# Shift_Register_2IO_Breakout.net
KiCad netlist of a schematic drawn in EAGLE
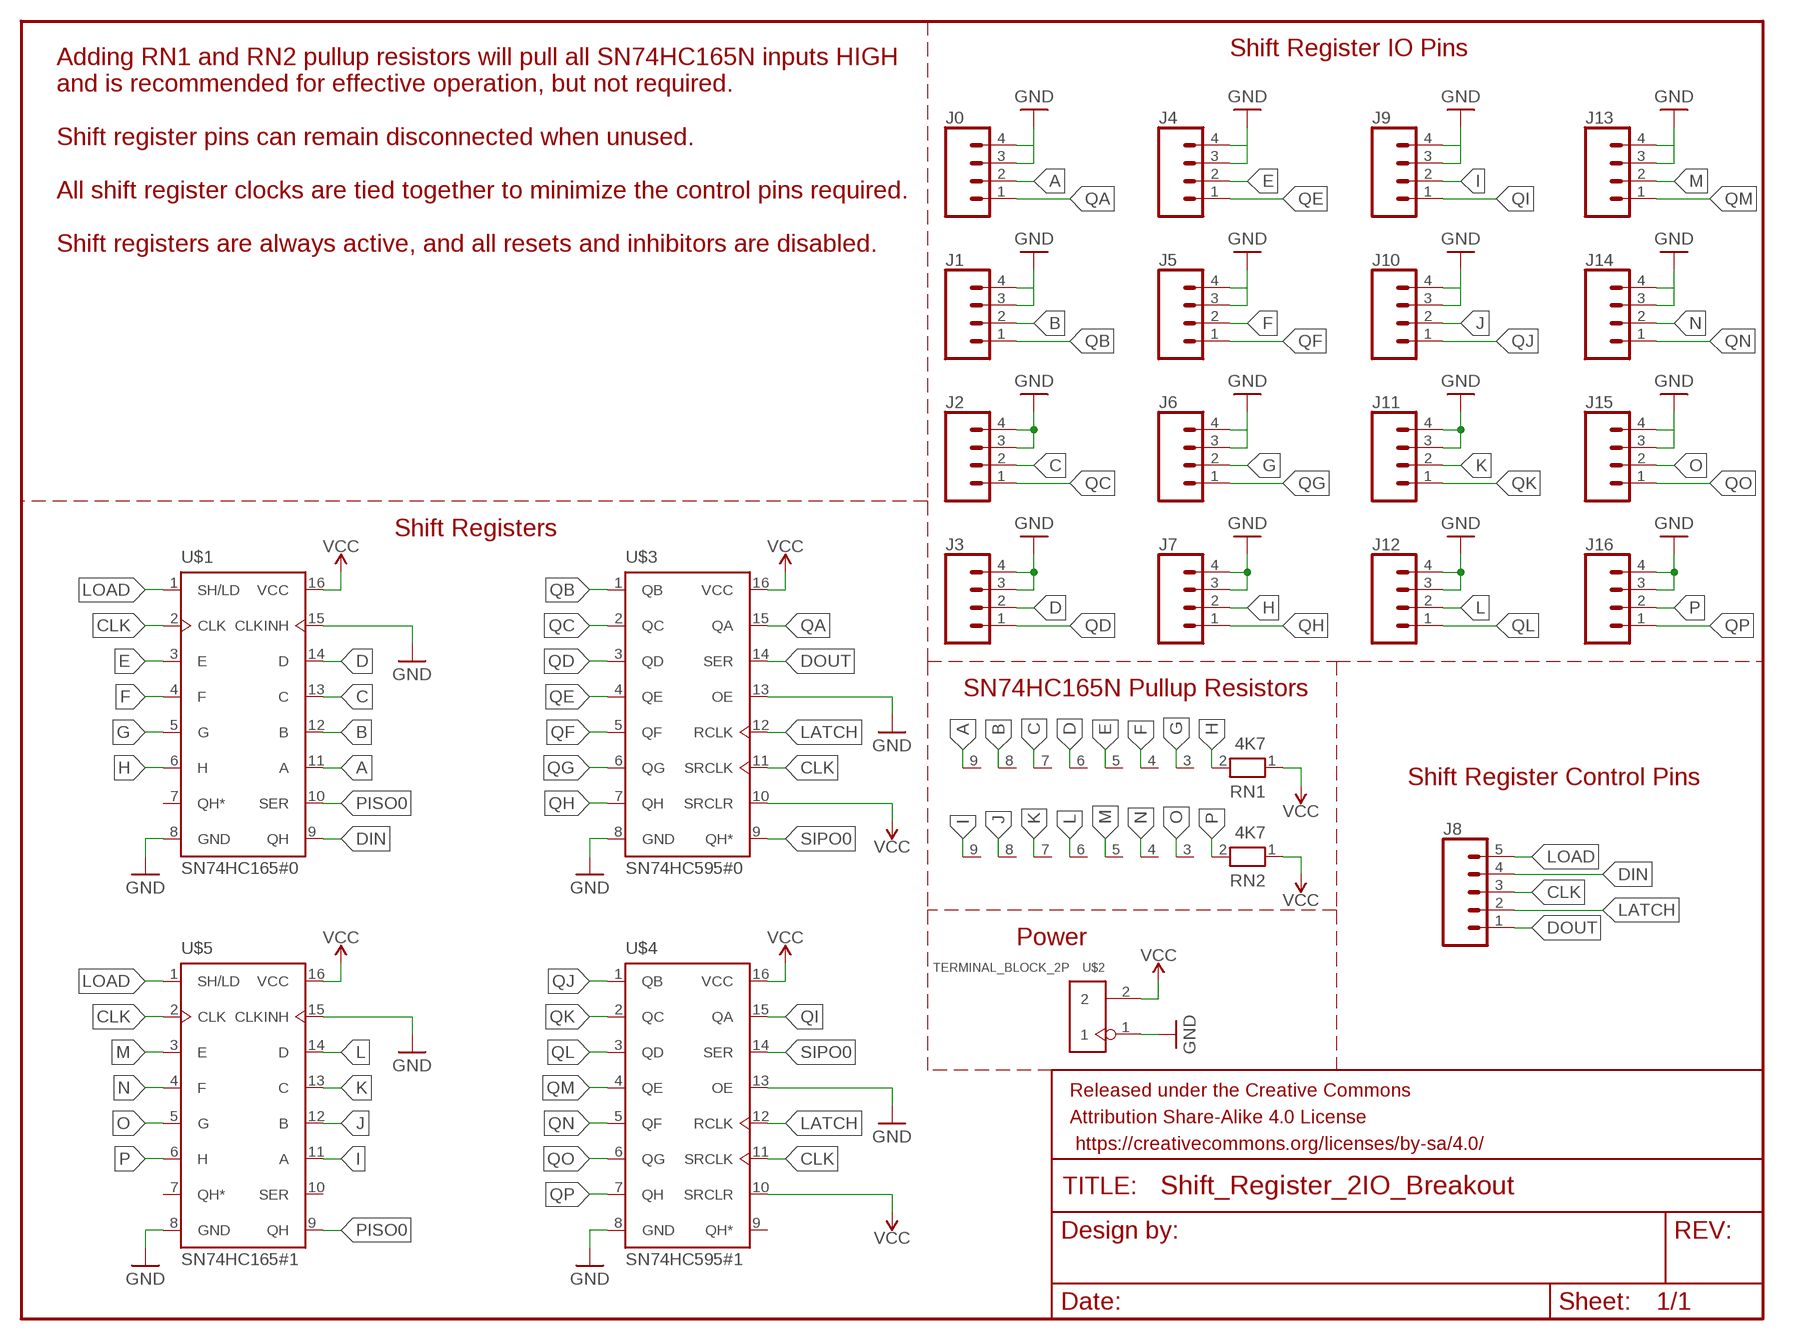
[diagram p0: schematic, sheet 1]

(export (version "E")
  (design (tool "Eeschema 10.0.6"))
  (components
    (comp (ref "FRAME2")
      (value "FRAME-LETTER")
      (footprint "eagle-import:CREATIVE_COMMONS")
      (libsource (lib "eagle-import") (part "FRAME-LETTER"))
    )
    (comp (ref "J0")
      (value "CONN_04")
      (footprint "eagle-import:1X04")
      (libsource (lib "eagle-import") (part "CONN_04"))
    )
    (comp (ref "J1")
      (value "CONN_04")
      (footprint "eagle-import:1X04")
      (libsource (lib "eagle-import") (part "CONN_04"))
    )
    (comp (ref "J2")
      (value "CONN_04")
      (footprint "eagle-import:1X04")
      (libsource (lib "eagle-import") (part "CONN_04"))
    )
    (comp (ref "J3")
      (value "CONN_04")
      (footprint "eagle-import:1X04")
      (libsource (lib "eagle-import") (part "CONN_04"))
    )
    (comp (ref "J4")
      (value "CONN_04")
      (footprint "eagle-import:1X04")
      (libsource (lib "eagle-import") (part "CONN_04"))
    )
    (comp (ref "J5")
      (value "CONN_04")
      (footprint "eagle-import:1X04")
      (libsource (lib "eagle-import") (part "CONN_04"))
    )
    (comp (ref "J6")
      (value "CONN_04")
      (footprint "eagle-import:1X04")
      (libsource (lib "eagle-import") (part "CONN_04"))
    )
    (comp (ref "J7")
      (value "CONN_04")
      (footprint "eagle-import:1X04")
      (libsource (lib "eagle-import") (part "CONN_04"))
    )
    (comp (ref "J8")
      (value "CONN_05")
      (footprint "eagle-import:1X05")
      (libsource (lib "eagle-import") (part "CONN_05"))
    )
    (comp (ref "J9")
      (value "CONN_04")
      (footprint "eagle-import:1X04")
      (libsource (lib "eagle-import") (part "CONN_04"))
    )
    (comp (ref "J10")
      (value "CONN_04")
      (footprint "eagle-import:1X04")
      (libsource (lib "eagle-import") (part "CONN_04"))
    )
    (comp (ref "J11")
      (value "CONN_04")
      (footprint "eagle-import:1X04")
      (libsource (lib "eagle-import") (part "CONN_04"))
    )
    (comp (ref "J12")
      (value "CONN_04")
      (footprint "eagle-import:1X04")
      (libsource (lib "eagle-import") (part "CONN_04"))
    )
    (comp (ref "J13")
      (value "CONN_04")
      (footprint "eagle-import:1X04")
      (libsource (lib "eagle-import") (part "CONN_04"))
    )
    (comp (ref "J14")
      (value "CONN_04")
      (footprint "eagle-import:1X04")
      (libsource (lib "eagle-import") (part "CONN_04"))
    )
    (comp (ref "J15")
      (value "CONN_04")
      (footprint "eagle-import:1X04")
      (libsource (lib "eagle-import") (part "CONN_04"))
    )
    (comp (ref "J16")
      (value "CONN_04")
      (footprint "eagle-import:1X04")
      (libsource (lib "eagle-import") (part "CONN_04"))
    )
    (comp (ref "RN1")
      (value "4K7")
      (footprint "eagle-import:RN-9")
      (libsource (lib "eagle-import") (part "RN08"))
    )
    (comp (ref "RN2")
      (value "4K7")
      (footprint "eagle-import:RN-9")
      (libsource (lib "eagle-import") (part "RN08"))
    )
    (comp (ref "U$1")
      (value "SN74HC165#0")
      (footprint "eagle-import:DIL16")
      (libsource (lib "eagle-import") (part "SN74HC165"))
    )
    (comp (ref "U$2")
      (value "TERMINAL_BLOCK_2P")
      (footprint "eagle-import:H2-5.0-10.5X8.0MM")
      (libsource (lib "eagle-import") (part "TERMINAL_BLOCK_2P"))
    )
    (comp (ref "U$3")
      (value "SN74HC595#0")
      (footprint "eagle-import:DIL16")
      (libsource (lib "eagle-import") (part "SN74HC595"))
    )
    (comp (ref "U$4")
      (value "SN74HC595#1")
      (footprint "eagle-import:DIL16")
      (libsource (lib "eagle-import") (part "SN74HC595"))
    )
    (comp (ref "U$5")
      (value "SN74HC165#1")
      (footprint "eagle-import:DIL16")
      (libsource (lib "eagle-import") (part "SN74HC165"))
    )
  )
  (nets
    (net (code "1") (name "A") (class "Default")
      (node (ref "J0") (pin "2") (pinfunction "2_2") (pintype "passive"))
      (node (ref "RN1") (pin "9") (pinfunction "9_9") (pintype "passive"))
      (node (ref "U$1") (pin "11") (pinfunction "A_11") (pintype "input"))
    )
    (net (code "2") (name "B") (class "Default")
      (node (ref "J1") (pin "2") (pinfunction "2_2") (pintype "passive"))
      (node (ref "RN1") (pin "8") (pinfunction "8_8") (pintype "passive"))
      (node (ref "U$1") (pin "12") (pinfunction "B_12") (pintype "input"))
    )
    (net (code "3") (name "C") (class "Default")
      (node (ref "J2") (pin "2") (pinfunction "2_2") (pintype "passive"))
      (node (ref "RN1") (pin "7") (pinfunction "7_7") (pintype "passive"))
      (node (ref "U$1") (pin "13") (pinfunction "C_13") (pintype "input"))
    )
    (net (code "4") (name "CLK") (class "Default")
      (node (ref "J8") (pin "3") (pinfunction "3_3") (pintype "passive"))
      (node (ref "U$1") (pin "2") (pinfunction "CLK_2") (pintype "input"))
      (node (ref "U$3") (pin "11") (pinfunction "SRCLK_11") (pintype "input"))
      (node (ref "U$4") (pin "11") (pinfunction "SRCLK_11") (pintype "input"))
      (node (ref "U$5") (pin "2") (pinfunction "CLK_2") (pintype "input"))
    )
    (net (code "5") (name "D") (class "Default")
      (node (ref "J3") (pin "2") (pinfunction "2_2") (pintype "passive"))
      (node (ref "RN1") (pin "6") (pinfunction "6_6") (pintype "passive"))
      (node (ref "U$1") (pin "14") (pinfunction "D_14") (pintype "input"))
    )
    (net (code "6") (name "DIN") (class "Default")
      (node (ref "J8") (pin "4") (pinfunction "4_4") (pintype "passive"))
      (node (ref "U$1") (pin "9") (pinfunction "QH_9") (pintype "output"))
    )
    (net (code "7") (name "DOUT") (class "Default")
      (node (ref "J8") (pin "1") (pinfunction "1_1") (pintype "passive"))
      (node (ref "U$3") (pin "14") (pinfunction "SER_14") (pintype "input"))
    )
    (net (code "8") (name "E") (class "Default")
      (node (ref "J4") (pin "2") (pinfunction "2_2") (pintype "passive"))
      (node (ref "RN1") (pin "5") (pinfunction "5_5") (pintype "passive"))
      (node (ref "U$1") (pin "3") (pinfunction "E_3") (pintype "input"))
    )
    (net (code "9") (name "F") (class "Default")
      (node (ref "J5") (pin "2") (pinfunction "2_2") (pintype "passive"))
      (node (ref "RN1") (pin "4") (pinfunction "4_4") (pintype "passive"))
      (node (ref "U$1") (pin "4") (pinfunction "F_4") (pintype "input"))
    )
    (net (code "10") (name "G") (class "Default")
      (node (ref "J6") (pin "2") (pinfunction "2_2") (pintype "passive"))
      (node (ref "RN1") (pin "3") (pinfunction "3_3") (pintype "passive"))
      (node (ref "U$1") (pin "5") (pinfunction "G_5") (pintype "input"))
    )
    (net (code "11") (name "GND") (class "Default")
      (node (ref "J0") (pin "3") (pinfunction "3_3") (pintype "passive"))
      (node (ref "J0") (pin "4") (pinfunction "4_4") (pintype "passive"))
      (node (ref "J1") (pin "3") (pinfunction "3_3") (pintype "passive"))
      (node (ref "J1") (pin "4") (pinfunction "4_4") (pintype "passive"))
      (node (ref "J10") (pin "3") (pinfunction "3_3") (pintype "passive"))
      (node (ref "J10") (pin "4") (pinfunction "4_4") (pintype "passive"))
      (node (ref "J11") (pin "3") (pinfunction "3_3") (pintype "passive"))
      (node (ref "J11") (pin "4") (pinfunction "4_4") (pintype "passive"))
      (node (ref "J12") (pin "3") (pinfunction "3_3") (pintype "passive"))
      (node (ref "J12") (pin "4") (pinfunction "4_4") (pintype "passive"))
      (node (ref "J13") (pin "3") (pinfunction "3_3") (pintype "passive"))
      (node (ref "J13") (pin "4") (pinfunction "4_4") (pintype "passive"))
      (node (ref "J14") (pin "3") (pinfunction "3_3") (pintype "passive"))
      (node (ref "J14") (pin "4") (pinfunction "4_4") (pintype "passive"))
      (node (ref "J15") (pin "3") (pinfunction "3_3") (pintype "passive"))
      (node (ref "J15") (pin "4") (pinfunction "4_4") (pintype "passive"))
      (node (ref "J16") (pin "3") (pinfunction "3_3") (pintype "passive"))
      (node (ref "J16") (pin "4") (pinfunction "4_4") (pintype "passive"))
      (node (ref "J2") (pin "3") (pinfunction "3_3") (pintype "passive"))
      (node (ref "J2") (pin "4") (pinfunction "4_4") (pintype "passive"))
      (node (ref "J3") (pin "3") (pinfunction "3_3") (pintype "passive"))
      (node (ref "J3") (pin "4") (pinfunction "4_4") (pintype "passive"))
      (node (ref "J4") (pin "3") (pinfunction "3_3") (pintype "passive"))
      (node (ref "J4") (pin "4") (pinfunction "4_4") (pintype "passive"))
      (node (ref "J5") (pin "3") (pinfunction "3_3") (pintype "passive"))
      (node (ref "J5") (pin "4") (pinfunction "4_4") (pintype "passive"))
      (node (ref "J6") (pin "3") (pinfunction "3_3") (pintype "passive"))
      (node (ref "J6") (pin "4") (pinfunction "4_4") (pintype "passive"))
      (node (ref "J7") (pin "3") (pinfunction "3_3") (pintype "passive"))
      (node (ref "J7") (pin "4") (pinfunction "4_4") (pintype "passive"))
      (node (ref "J9") (pin "3") (pinfunction "3_3") (pintype "passive"))
      (node (ref "J9") (pin "4") (pinfunction "4_4") (pintype "passive"))
      (node (ref "U$1") (pin "15") (pinfunction "CLKINH_15") (pintype "input"))
      (node (ref "U$1") (pin "8") (pinfunction "GND_8") (pintype "power_in"))
      (node (ref "U$2") (pin "1") (pinfunction "1_1") (pintype "bidirectional"))
      (node (ref "U$3") (pin "13") (pinfunction "OE_13") (pintype "open_collector"))
      (node (ref "U$3") (pin "8") (pinfunction "GND_8") (pintype "power_in"))
      (node (ref "U$4") (pin "13") (pinfunction "OE_13") (pintype "open_collector"))
      (node (ref "U$4") (pin "8") (pinfunction "GND_8") (pintype "power_in"))
      (node (ref "U$5") (pin "15") (pinfunction "CLKINH_15") (pintype "input"))
      (node (ref "U$5") (pin "8") (pinfunction "GND_8") (pintype "power_in"))
    )
    (net (code "12") (name "H") (class "Default")
      (node (ref "J7") (pin "2") (pinfunction "2_2") (pintype "passive"))
      (node (ref "RN1") (pin "2") (pinfunction "2_2") (pintype "passive"))
      (node (ref "U$1") (pin "6") (pinfunction "H_6") (pintype "input"))
    )
    (net (code "13") (name "I") (class "Default")
      (node (ref "J9") (pin "2") (pinfunction "2_2") (pintype "passive"))
      (node (ref "RN2") (pin "9") (pinfunction "9_9") (pintype "passive"))
      (node (ref "U$5") (pin "11") (pinfunction "A_11") (pintype "input"))
    )
    (net (code "14") (name "J") (class "Default")
      (node (ref "J10") (pin "2") (pinfunction "2_2") (pintype "passive"))
      (node (ref "RN2") (pin "8") (pinfunction "8_8") (pintype "passive"))
      (node (ref "U$5") (pin "12") (pinfunction "B_12") (pintype "input"))
    )
    (net (code "15") (name "K") (class "Default")
      (node (ref "J11") (pin "2") (pinfunction "2_2") (pintype "passive"))
      (node (ref "RN2") (pin "7") (pinfunction "7_7") (pintype "passive"))
      (node (ref "U$5") (pin "13") (pinfunction "C_13") (pintype "input"))
    )
    (net (code "16") (name "L") (class "Default")
      (node (ref "J12") (pin "2") (pinfunction "2_2") (pintype "passive"))
      (node (ref "RN2") (pin "6") (pinfunction "6_6") (pintype "passive"))
      (node (ref "U$5") (pin "14") (pinfunction "D_14") (pintype "input"))
    )
    (net (code "17") (name "LATCH") (class "Default")
      (node (ref "J8") (pin "2") (pinfunction "2_2") (pintype "passive"))
      (node (ref "U$3") (pin "12") (pinfunction "RCLK_12") (pintype "input"))
      (node (ref "U$4") (pin "12") (pinfunction "RCLK_12") (pintype "input"))
    )
    (net (code "18") (name "LOAD") (class "Default")
      (node (ref "J8") (pin "5") (pinfunction "5_5") (pintype "passive"))
      (node (ref "U$1") (pin "1") (pinfunction "SH/LD_1") (pintype "open_collector"))
      (node (ref "U$5") (pin "1") (pinfunction "SH/LD_1") (pintype "open_collector"))
    )
    (net (code "19") (name "M") (class "Default")
      (node (ref "J13") (pin "2") (pinfunction "2_2") (pintype "passive"))
      (node (ref "RN2") (pin "5") (pinfunction "5_5") (pintype "passive"))
      (node (ref "U$5") (pin "3") (pinfunction "E_3") (pintype "input"))
    )
    (net (code "20") (name "N") (class "Default")
      (node (ref "J14") (pin "2") (pinfunction "2_2") (pintype "passive"))
      (node (ref "RN2") (pin "4") (pinfunction "4_4") (pintype "passive"))
      (node (ref "U$5") (pin "4") (pinfunction "F_4") (pintype "input"))
    )
    (net (code "21") (name "O") (class "Default")
      (node (ref "J15") (pin "2") (pinfunction "2_2") (pintype "passive"))
      (node (ref "RN2") (pin "3") (pinfunction "3_3") (pintype "passive"))
      (node (ref "U$5") (pin "5") (pinfunction "G_5") (pintype "input"))
    )
    (net (code "22") (name "P") (class "Default")
      (node (ref "J16") (pin "2") (pinfunction "2_2") (pintype "passive"))
      (node (ref "RN2") (pin "2") (pinfunction "2_2") (pintype "passive"))
      (node (ref "U$5") (pin "6") (pinfunction "H_6") (pintype "input"))
    )
    (net (code "23") (name "PISO0") (class "Default")
      (node (ref "U$1") (pin "10") (pinfunction "SER_10") (pintype "input"))
      (node (ref "U$5") (pin "9") (pinfunction "QH_9") (pintype "output"))
    )
    (net (code "24") (name "QA") (class "Default")
      (node (ref "J0") (pin "1") (pinfunction "1_1") (pintype "passive"))
      (node (ref "U$3") (pin "15") (pinfunction "QA_15") (pintype "output"))
    )
    (net (code "25") (name "QB") (class "Default")
      (node (ref "J1") (pin "1") (pinfunction "1_1") (pintype "passive"))
      (node (ref "U$3") (pin "1") (pinfunction "QB_1") (pintype "output"))
    )
    (net (code "26") (name "QC") (class "Default")
      (node (ref "J2") (pin "1") (pinfunction "1_1") (pintype "passive"))
      (node (ref "U$3") (pin "2") (pinfunction "QC_2") (pintype "output"))
    )
    (net (code "27") (name "QD") (class "Default")
      (node (ref "J3") (pin "1") (pinfunction "1_1") (pintype "passive"))
      (node (ref "U$3") (pin "3") (pinfunction "QD_3") (pintype "output"))
    )
    (net (code "28") (name "QE") (class "Default")
      (node (ref "J4") (pin "1") (pinfunction "1_1") (pintype "passive"))
      (node (ref "U$3") (pin "4") (pinfunction "QE_4") (pintype "output"))
    )
    (net (code "29") (name "QF") (class "Default")
      (node (ref "J5") (pin "1") (pinfunction "1_1") (pintype "passive"))
      (node (ref "U$3") (pin "5") (pinfunction "QF_5") (pintype "output"))
    )
    (net (code "30") (name "QG") (class "Default")
      (node (ref "J6") (pin "1") (pinfunction "1_1") (pintype "passive"))
      (node (ref "U$3") (pin "6") (pinfunction "QG_6") (pintype "output"))
    )
    (net (code "31") (name "QH") (class "Default")
      (node (ref "J7") (pin "1") (pinfunction "1_1") (pintype "passive"))
      (node (ref "U$3") (pin "7") (pinfunction "QH_7") (pintype "output"))
    )
    (net (code "32") (name "QI") (class "Default")
      (node (ref "J9") (pin "1") (pinfunction "1_1") (pintype "passive"))
      (node (ref "U$4") (pin "15") (pinfunction "QA_15") (pintype "output"))
    )
    (net (code "33") (name "QJ") (class "Default")
      (node (ref "J10") (pin "1") (pinfunction "1_1") (pintype "passive"))
      (node (ref "U$4") (pin "1") (pinfunction "QB_1") (pintype "output"))
    )
    (net (code "34") (name "QK") (class "Default")
      (node (ref "J11") (pin "1") (pinfunction "1_1") (pintype "passive"))
      (node (ref "U$4") (pin "2") (pinfunction "QC_2") (pintype "output"))
    )
    (net (code "35") (name "QL") (class "Default")
      (node (ref "J12") (pin "1") (pinfunction "1_1") (pintype "passive"))
      (node (ref "U$4") (pin "3") (pinfunction "QD_3") (pintype "output"))
    )
    (net (code "36") (name "QM") (class "Default")
      (node (ref "J13") (pin "1") (pinfunction "1_1") (pintype "passive"))
      (node (ref "U$4") (pin "4") (pinfunction "QE_4") (pintype "output"))
    )
    (net (code "37") (name "QN") (class "Default")
      (node (ref "J14") (pin "1") (pinfunction "1_1") (pintype "passive"))
      (node (ref "U$4") (pin "5") (pinfunction "QF_5") (pintype "output"))
    )
    (net (code "38") (name "QO") (class "Default")
      (node (ref "J15") (pin "1") (pinfunction "1_1") (pintype "passive"))
      (node (ref "U$4") (pin "6") (pinfunction "QG_6") (pintype "output"))
    )
    (net (code "39") (name "QP") (class "Default")
      (node (ref "J16") (pin "1") (pinfunction "1_1") (pintype "passive"))
      (node (ref "U$4") (pin "7") (pinfunction "QH_7") (pintype "output"))
    )
    (net (code "40") (name "SIPO0") (class "Default")
      (node (ref "U$3") (pin "9") (pinfunction "QH*_9") (pintype "output"))
      (node (ref "U$4") (pin "14") (pinfunction "SER_14") (pintype "input"))
    )
    (net (code "41") (name "VCC") (class "Default")
      (node (ref "RN1") (pin "1") (pinfunction "1_1") (pintype "passive"))
      (node (ref "RN2") (pin "1") (pinfunction "1_1") (pintype "passive"))
      (node (ref "U$1") (pin "16") (pinfunction "VCC_16") (pintype "power_in"))
      (node (ref "U$2") (pin "2") (pinfunction "2_2") (pintype "bidirectional"))
      (node (ref "U$3") (pin "10") (pinfunction "SRCLR_10") (pintype "open_collector"))
      (node (ref "U$3") (pin "16") (pinfunction "VCC_16") (pintype "power_in"))
      (node (ref "U$4") (pin "10") (pinfunction "SRCLR_10") (pintype "open_collector"))
      (node (ref "U$4") (pin "16") (pinfunction "VCC_16") (pintype "power_in"))
      (node (ref "U$5") (pin "16") (pinfunction "VCC_16") (pintype "power_in"))
    )
    (net (code "42") (name "unconnected-(U$1-QH*-Pad7)") (class "Default")
      (node (ref "U$1") (pin "7") (pinfunction "QH*_7") (pintype "output"))
    )
    (net (code "43") (name "unconnected-(U$4-QH*-Pad9)") (class "Default")
      (node (ref "U$4") (pin "9") (pinfunction "QH*_9") (pintype "output"))
    )
    (net (code "44") (name "unconnected-(U$5-QH*-Pad7)") (class "Default")
      (node (ref "U$5") (pin "7") (pinfunction "QH*_7") (pintype "output"))
    )
    (net (code "45") (name "unconnected-(U$5-SER-Pad10)") (class "Default")
      (node (ref "U$5") (pin "10") (pinfunction "SER_10") (pintype "input"))
    )
  )
)
